# LI.net
KiCad netlist of a schematic drawn in EAGLE
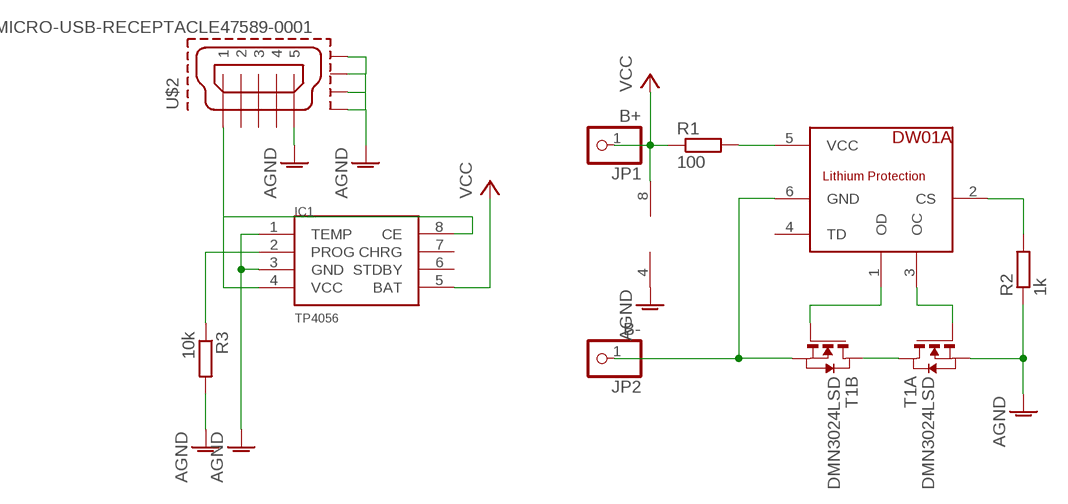
[diagram p0: schematic, sheet 1]

(export (version "E")
  (design (tool "Eeschema 10.0.6"))
  (components
    (comp (ref "IC1")
      (value "TP4056")
      (footprint "eagle-import:SOP-8")
      (libsource (lib "eagle-import") (part "TP4056"))
    )
    (comp (ref "IC2")
      (value "TL082D")
      (footprint "eagle-import:SO08")
      (libsource (lib "eagle-import") (part "TL082D"))
    )
    (comp (ref "JP1")
      (value "B+")
      (footprint "eagle-import:1X01")
      (libsource (lib "eagle-import") (part "PINHD-1X1"))
    )
    (comp (ref "JP2")
      (value "B-")
      (footprint "eagle-import:1X01")
      (libsource (lib "eagle-import") (part "PINHD-1X1"))
    )
    (comp (ref "R1")
      (value "100")
      (footprint "eagle-import:R0805")
      (libsource (lib "eagle-import") (part "R-EU_R0805"))
    )
    (comp (ref "R2")
      (value "1k")
      (footprint "eagle-import:R0805")
      (libsource (lib "eagle-import") (part "R-EU_R0805"))
    )
    (comp (ref "R3")
      (value "10k")
      (footprint "eagle-import:R0805")
      (libsource (lib "eagle-import") (part "R-EU_R0805"))
    )
    (comp (ref "T1")
      (value "DMN3024LSD")
      (footprint "eagle-import:TSSOP-8")
      (libsource (lib "eagle-import") (part "DMN3024LSD"))
    )
    (comp (ref "U$1")
      (value "DW01A")
      (footprint "eagle-import:SOT23-6")
      (libsource (lib "eagle-import") (part "DW01A"))
    )
    (comp (ref "U$2")
      (value "MICRO-USB-RECEPTACLE47589-0001")
      (footprint "eagle-import:47589-0001")
      (libsource (lib "eagle-import") (part "MICRO-USB-RECEPTACLE47589-0001"))
    )
  )
  (nets
    (net (code "1") (name "AGND") (class "Default")
      (node (ref "IC1") (pin "1") (pinfunction "TEMP_1") (pintype "bidirectional"))
      (node (ref "IC1") (pin "3") (pinfunction "GND_3") (pintype "bidirectional"))
      (node (ref "IC2") (pin "4") (pinfunction "V-_4") (pintype "power_in"))
      (node (ref "R2") (pin "1") (pinfunction "1_1") (pintype "passive"))
      (node (ref "R3") (pin "2") (pinfunction "2_2") (pintype "passive"))
      (node (ref "T1") (pin "2") (pinfunction "S_2") (pintype "passive"))
      (node (ref "T1") (pin "3") (pinfunction "S_3") (pintype "passive"))
      (node (ref "U$2") (pin "5") (pinfunction "5_5") (pintype "input"))
      (node (ref "U$2") (pin "CASING1") (pinfunction "GND1_CASING1") (pintype "bidirectional"))
      (node (ref "U$2") (pin "CASING2") (pinfunction "GND2_CASING2") (pintype "bidirectional"))
      (node (ref "U$2") (pin "CASING3") (pinfunction "GND3_CASING3") (pintype "bidirectional"))
      (node (ref "U$2") (pin "CASING4") (pinfunction "GND4_CASING4") (pintype "bidirectional"))
    )
    (net (code "2") (name "Net-(IC1-CE)") (class "Default")
      (node (ref "IC1") (pin "4") (pinfunction "VCC_4") (pintype "bidirectional"))
      (node (ref "IC1") (pin "8") (pinfunction "CE_8") (pintype "bidirectional"))
      (node (ref "U$2") (pin "1") (pinfunction "1_1") (pintype "input"))
    )
    (net (code "3") (name "Net-(IC1-PROG)") (class "Default")
      (node (ref "IC1") (pin "2") (pinfunction "PROG_2") (pintype "bidirectional"))
      (node (ref "R3") (pin "1") (pinfunction "1_1") (pintype "passive"))
    )
    (net (code "4") (name "Net-(T1A-D)") (class "Default")
      (node (ref "T1") (pin "1") (pinfunction "D_1") (pintype "passive"))
      (node (ref "T1") (pin "8") (pinfunction "D_8") (pintype "passive"))
    )
    (net (code "5") (name "Net-(T1A-G)") (class "Default")
      (node (ref "T1") (pin "4") (pinfunction "G_4") (pintype "passive"))
      (node (ref "U$1") (pin "3") (pinfunction "OC_3") (pintype "bidirectional"))
    )
    (net (code "6") (name "Net-(T1B-G)") (class "Default")
      (node (ref "T1") (pin "5") (pinfunction "G_5") (pintype "passive"))
      (node (ref "U$1") (pin "1") (pinfunction "OD_1") (pintype "bidirectional"))
    )
    (net (code "7") (name "Net-(U$1-CS)") (class "Default")
      (node (ref "R2") (pin "2") (pinfunction "2_2") (pintype "passive"))
      (node (ref "U$1") (pin "2") (pinfunction "CS_2") (pintype "bidirectional"))
    )
    (net (code "8") (name "Net-(U$1-GND)") (class "Default")
      (node (ref "JP2") (pin "1") (pinfunction "1_1") (pintype "passive"))
      (node (ref "T1") (pin "6") (pinfunction "S_6") (pintype "passive"))
      (node (ref "T1") (pin "7") (pinfunction "S_7") (pintype "passive"))
      (node (ref "U$1") (pin "6") (pinfunction "GND_6") (pintype "bidirectional"))
    )
    (net (code "9") (name "Net-(U$1-VCC)") (class "Default")
      (node (ref "R1") (pin "2") (pinfunction "2_2") (pintype "passive"))
      (node (ref "U$1") (pin "5") (pinfunction "VCC_5") (pintype "bidirectional"))
    )
    (net (code "10") (name "VCC") (class "Default")
      (node (ref "IC1") (pin "5") (pinfunction "BAT_5") (pintype "bidirectional"))
      (node (ref "IC2") (pin "8") (pinfunction "V+_8") (pintype "power_in"))
      (node (ref "JP1") (pin "1") (pinfunction "1_1") (pintype "passive"))
      (node (ref "R1") (pin "1") (pinfunction "1_1") (pintype "passive"))
    )
    (net (code "11") (name "unconnected-(IC1-CHRG-Pad7)") (class "Default")
      (node (ref "IC1") (pin "7") (pinfunction "CHRG_7") (pintype "bidirectional"))
    )
    (net (code "12") (name "unconnected-(IC1-STDBY-Pad6)") (class "Default")
      (node (ref "IC1") (pin "6") (pinfunction "STDBY_6") (pintype "bidirectional"))
    )
    (net (code "13") (name "unconnected-(U$1-TD-Pad4)") (class "Default")
      (node (ref "U$1") (pin "4") (pinfunction "TD_4") (pintype "bidirectional"))
    )
    (net (code "14") (name "unconnected-(U$2-Pad2)") (class "Default")
      (node (ref "U$2") (pin "2") (pinfunction "2_2") (pintype "input"))
    )
    (net (code "15") (name "unconnected-(U$2-Pad3)") (class "Default")
      (node (ref "U$2") (pin "3") (pinfunction "3_3") (pintype "input"))
    )
    (net (code "16") (name "unconnected-(U$2-Pad4)") (class "Default")
      (node (ref "U$2") (pin "4") (pinfunction "4_4") (pintype "input"))
    )
  )
)
